# AJH_MM_v1_0.net
KiCad netlist of a schematic drawn in EAGLE
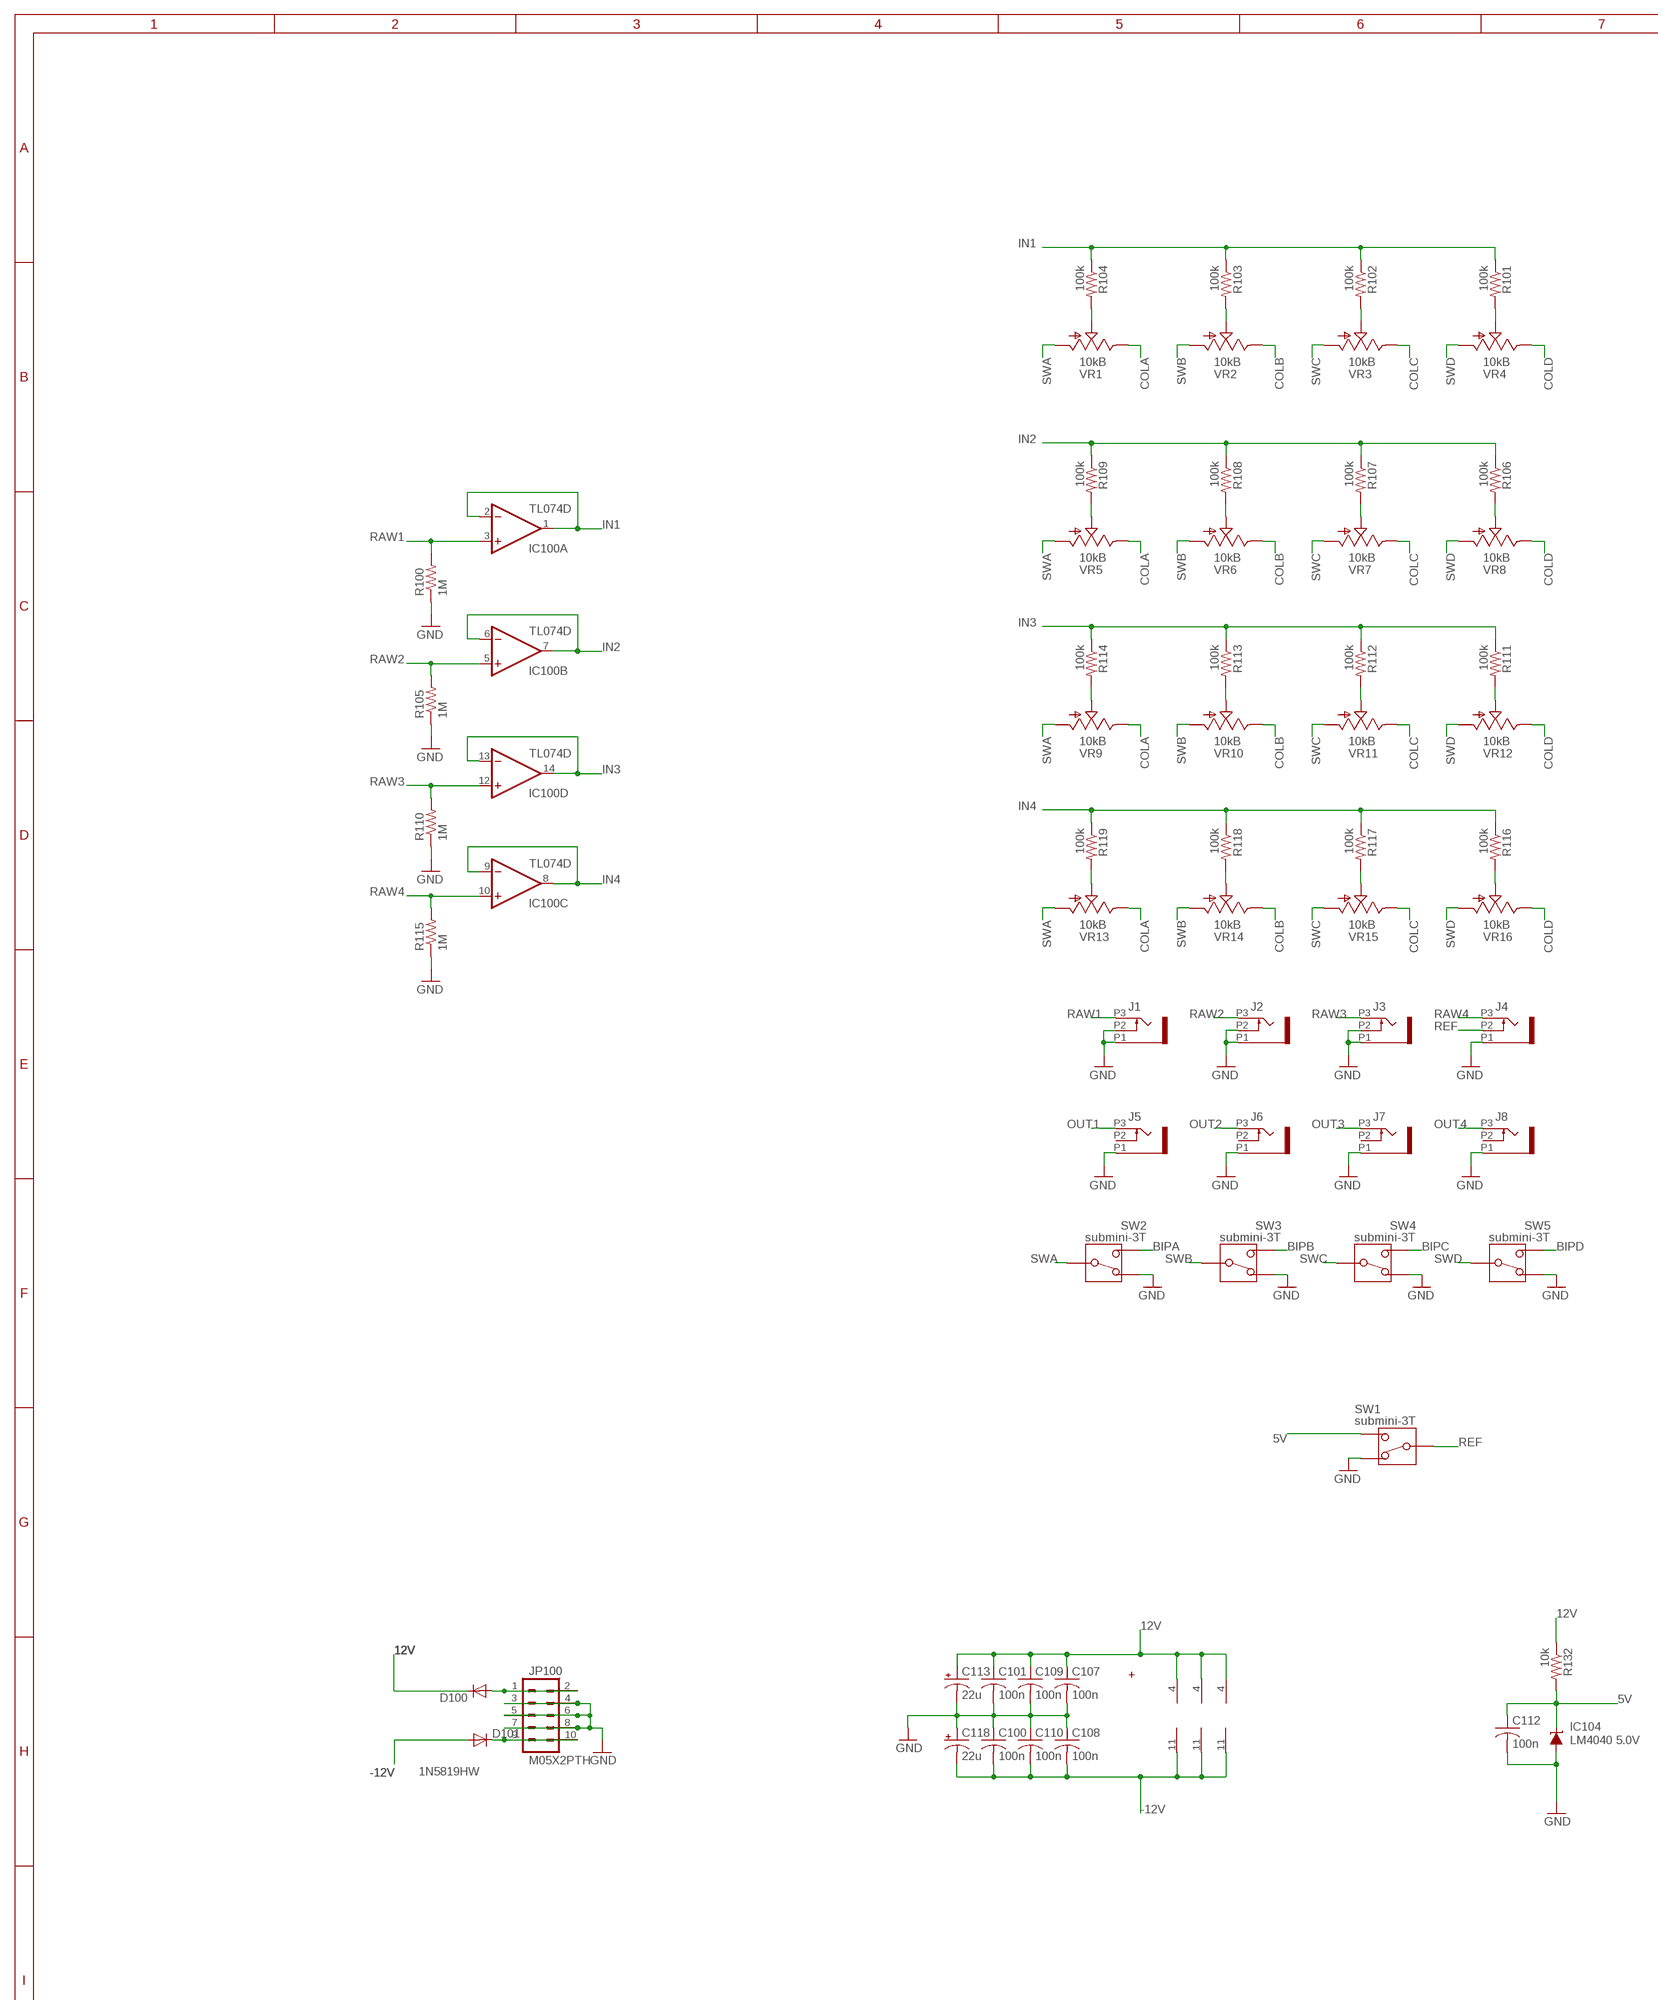
[diagram p0: schematic, sheet 1, part 1 of 2]
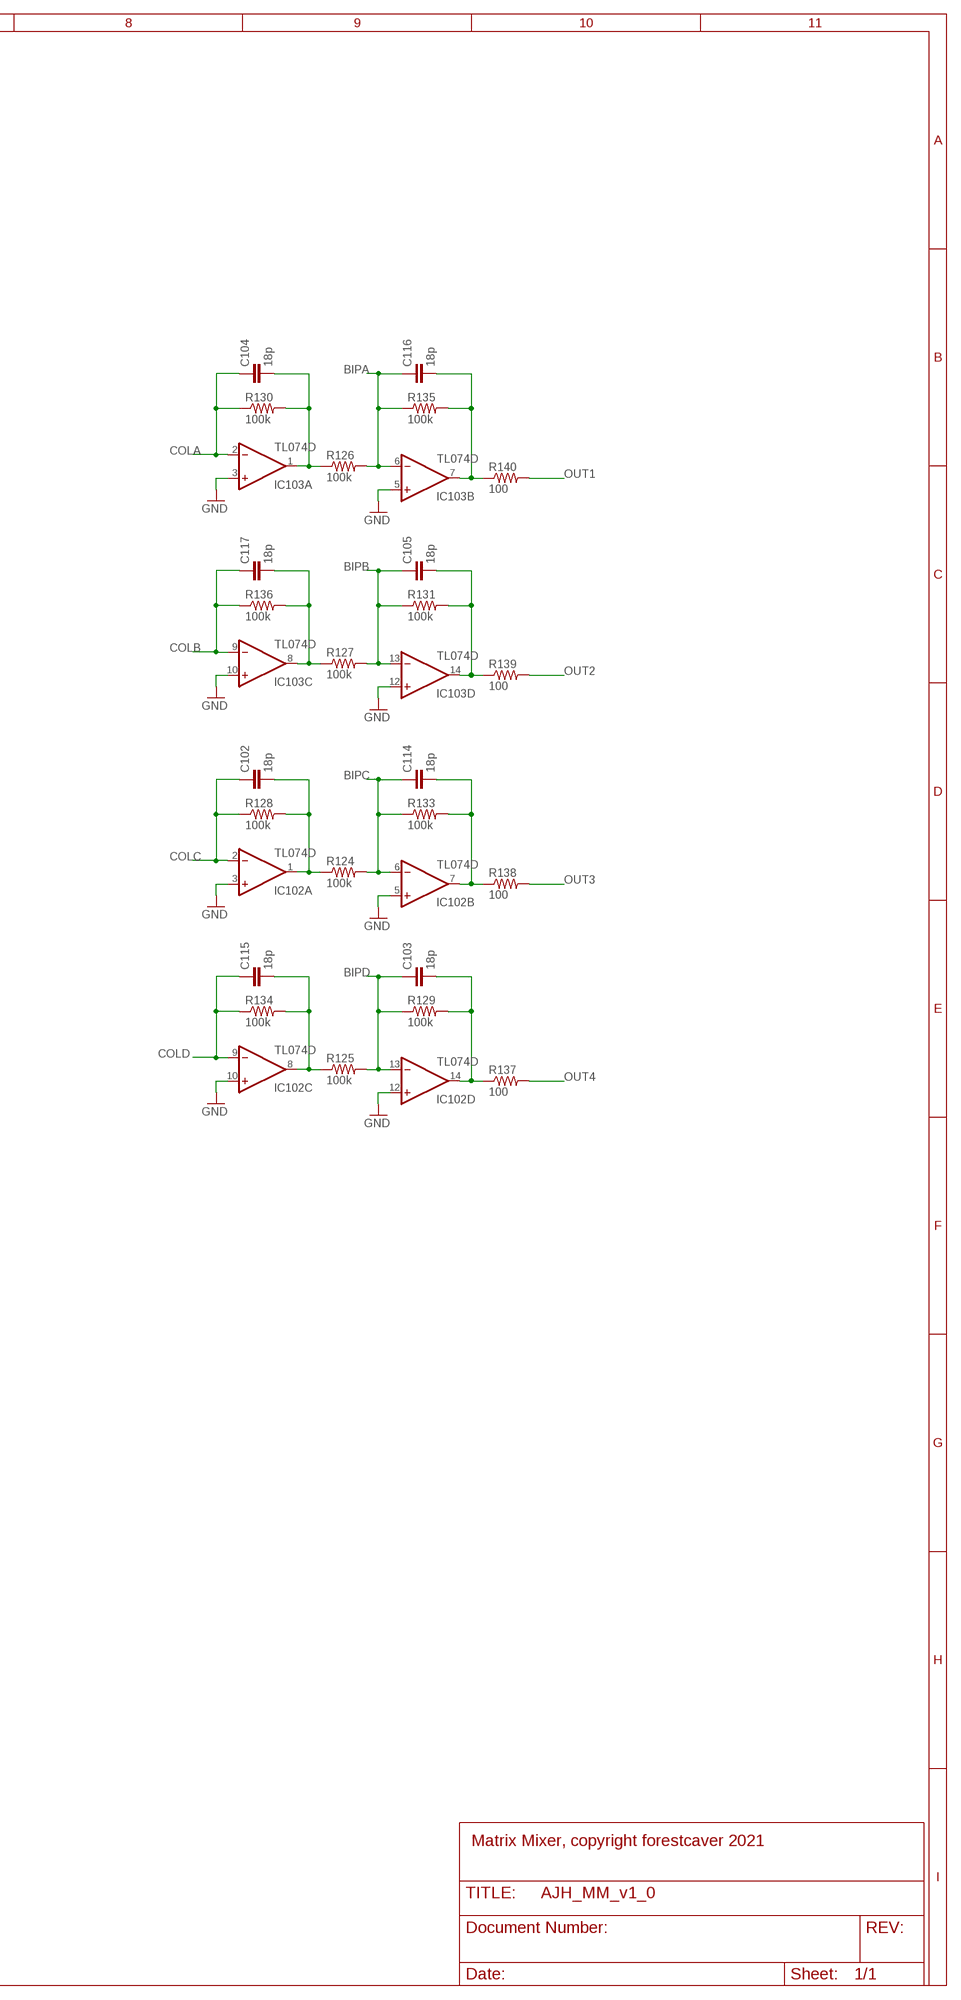
[diagram p1: schematic, sheet 1, part 2 of 2]

(export (version "E")
  (design (tool "Eeschema 10.0.6"))
  (components
    (comp (ref "C100")
      (value "100n")
      (footprint "eagle-import:C0603")
      (libsource (lib "eagle-import") (part "C-USC0603"))
    )
    (comp (ref "C101")
      (value "100n")
      (footprint "eagle-import:C0603")
      (libsource (lib "eagle-import") (part "C-USC0603"))
    )
    (comp (ref "C102")
      (value "18p")
      (footprint "eagle-import:C0603")
      (libsource (lib "eagle-import") (part "C-EUC0603"))
    )
    (comp (ref "C103")
      (value "18p")
      (footprint "eagle-import:C0603")
      (libsource (lib "eagle-import") (part "C-EUC0603"))
    )
    (comp (ref "C104")
      (value "18p")
      (footprint "eagle-import:C0603")
      (libsource (lib "eagle-import") (part "C-EUC0603"))
    )
    (comp (ref "C105")
      (value "18p")
      (footprint "eagle-import:C0603")
      (libsource (lib "eagle-import") (part "C-EUC0603"))
    )
    (comp (ref "C107")
      (value "100n")
      (footprint "eagle-import:C0603")
      (libsource (lib "eagle-import") (part "C-USC0603"))
    )
    (comp (ref "C108")
      (value "100n")
      (footprint "eagle-import:C0603")
      (libsource (lib "eagle-import") (part "C-USC0603"))
    )
    (comp (ref "C109")
      (value "100n")
      (footprint "eagle-import:C0603")
      (libsource (lib "eagle-import") (part "C-USC0603"))
    )
    (comp (ref "C110")
      (value "100n")
      (footprint "eagle-import:C0603")
      (libsource (lib "eagle-import") (part "C-USC0603"))
    )
    (comp (ref "C112")
      (value "100n")
      (footprint "eagle-import:C0603")
      (libsource (lib "eagle-import") (part "C-USC0603"))
    )
    (comp (ref "C113")
      (value "22u")
      (footprint "eagle-import:PANASONIC_B")
      (libsource (lib "eagle-import") (part "CPOL-USB"))
    )
    (comp (ref "C114")
      (value "18p")
      (footprint "eagle-import:C0603")
      (libsource (lib "eagle-import") (part "C-EUC0603"))
    )
    (comp (ref "C115")
      (value "18p")
      (footprint "eagle-import:C0603")
      (libsource (lib "eagle-import") (part "C-EUC0603"))
    )
    (comp (ref "C116")
      (value "18p")
      (footprint "eagle-import:C0603")
      (libsource (lib "eagle-import") (part "C-EUC0603"))
    )
    (comp (ref "C117")
      (value "18p")
      (footprint "eagle-import:C0603")
      (libsource (lib "eagle-import") (part "C-EUC0603"))
    )
    (comp (ref "C118")
      (value "22u")
      (footprint "eagle-import:PANASONIC_B")
      (libsource (lib "eagle-import") (part "CPOL-USB"))
    )
    (comp (ref "D100")
      (value "1N5819HW")
      (footprint "eagle-import:SOD123")
      (libsource (lib "eagle-import") (part "DIODE-SOD123"))
    )
    (comp (ref "D101")
      (value "1N5819HW")
      (footprint "eagle-import:SOD123")
      (libsource (lib "eagle-import") (part "DIODE-SOD123"))
    )
    (comp (ref "IC100")
      (value "TL074D")
      (footprint "eagle-import:SO14")
      (libsource (lib "eagle-import") (part "TL074D"))
    )
    (comp (ref "IC102")
      (value "TL074D")
      (footprint "eagle-import:SO14")
      (libsource (lib "eagle-import") (part "TL074D"))
    )
    (comp (ref "IC103")
      (value "TL074D")
      (footprint "eagle-import:SO14")
      (libsource (lib "eagle-import") (part "TL074D"))
    )
    (comp (ref "IC104")
      (value "LM4040 5.0V")
      (footprint "eagle-import:DBZ_R-PDSO-G3")
      (libsource (lib "eagle-import") (part "LM4041DBZC12"))
    )
    (comp (ref "J1")
      (value "PJ301_THONKICONN6")
      (footprint "eagle-import:WQP_PJ_301M6")
      (libsource (lib "eagle-import") (part "PJ301_THONKICONN6"))
    )
    (comp (ref "J2")
      (value "PJ301_THONKICONN6")
      (footprint "eagle-import:WQP_PJ_301M6")
      (libsource (lib "eagle-import") (part "PJ301_THONKICONN6"))
    )
    (comp (ref "J3")
      (value "PJ301_THONKICONN6")
      (footprint "eagle-import:WQP_PJ_301M6")
      (libsource (lib "eagle-import") (part "PJ301_THONKICONN6"))
    )
    (comp (ref "J4")
      (value "PJ301_THONKICONN6")
      (footprint "eagle-import:WQP_PJ_301M6")
      (libsource (lib "eagle-import") (part "PJ301_THONKICONN6"))
    )
    (comp (ref "J5")
      (value "PJ301_THONKICONN6")
      (footprint "eagle-import:WQP_PJ_301M6")
      (libsource (lib "eagle-import") (part "PJ301_THONKICONN6"))
    )
    (comp (ref "J6")
      (value "PJ301_THONKICONN6")
      (footprint "eagle-import:WQP_PJ_301M6")
      (libsource (lib "eagle-import") (part "PJ301_THONKICONN6"))
    )
    (comp (ref "J7")
      (value "PJ301_THONKICONN6")
      (footprint "eagle-import:WQP_PJ_301M6")
      (libsource (lib "eagle-import") (part "PJ301_THONKICONN6"))
    )
    (comp (ref "J8")
      (value "PJ301_THONKICONN6")
      (footprint "eagle-import:WQP_PJ_301M6")
      (libsource (lib "eagle-import") (part "PJ301_THONKICONN6"))
    )
    (comp (ref "JP100")
      (value "M05X2PTH")
      (footprint "eagle-import:AVR_ICSP")
      (libsource (lib "eagle-import") (part "M05X2PTH"))
    )
    (comp (ref "R100")
      (value "1M")
      (footprint "eagle-import:R0603")
      (libsource (lib "eagle-import") (part "R-US_R0603"))
    )
    (comp (ref "R101")
      (value "100k")
      (footprint "eagle-import:R0603")
      (libsource (lib "eagle-import") (part "R-US_R0603"))
    )
    (comp (ref "R102")
      (value "100k")
      (footprint "eagle-import:R0603")
      (libsource (lib "eagle-import") (part "R-US_R0603"))
    )
    (comp (ref "R103")
      (value "100k")
      (footprint "eagle-import:R0603")
      (libsource (lib "eagle-import") (part "R-US_R0603"))
    )
    (comp (ref "R104")
      (value "100k")
      (footprint "eagle-import:R0603")
      (libsource (lib "eagle-import") (part "R-US_R0603"))
    )
    (comp (ref "R105")
      (value "1M")
      (footprint "eagle-import:R0603")
      (libsource (lib "eagle-import") (part "R-US_R0603"))
    )
    (comp (ref "R106")
      (value "100k")
      (footprint "eagle-import:R0603")
      (libsource (lib "eagle-import") (part "R-US_R0603"))
    )
    (comp (ref "R107")
      (value "100k")
      (footprint "eagle-import:R0603")
      (libsource (lib "eagle-import") (part "R-US_R0603"))
    )
    (comp (ref "R108")
      (value "100k")
      (footprint "eagle-import:R0603")
      (libsource (lib "eagle-import") (part "R-US_R0603"))
    )
    (comp (ref "R109")
      (value "100k")
      (footprint "eagle-import:R0603")
      (libsource (lib "eagle-import") (part "R-US_R0603"))
    )
    (comp (ref "R110")
      (value "1M")
      (footprint "eagle-import:R0603")
      (libsource (lib "eagle-import") (part "R-US_R0603"))
    )
    (comp (ref "R111")
      (value "100k")
      (footprint "eagle-import:R0603")
      (libsource (lib "eagle-import") (part "R-US_R0603"))
    )
    (comp (ref "R112")
      (value "100k")
      (footprint "eagle-import:R0603")
      (libsource (lib "eagle-import") (part "R-US_R0603"))
    )
    (comp (ref "R113")
      (value "100k")
      (footprint "eagle-import:R0603")
      (libsource (lib "eagle-import") (part "R-US_R0603"))
    )
    (comp (ref "R114")
      (value "100k")
      (footprint "eagle-import:R0603")
      (libsource (lib "eagle-import") (part "R-US_R0603"))
    )
    (comp (ref "R115")
      (value "1M")
      (footprint "eagle-import:R0603")
      (libsource (lib "eagle-import") (part "R-US_R0603"))
    )
    (comp (ref "R116")
      (value "100k")
      (footprint "eagle-import:R0603")
      (libsource (lib "eagle-import") (part "R-US_R0603"))
    )
    (comp (ref "R117")
      (value "100k")
      (footprint "eagle-import:R0603")
      (libsource (lib "eagle-import") (part "R-US_R0603"))
    )
    (comp (ref "R118")
      (value "100k")
      (footprint "eagle-import:R0603")
      (libsource (lib "eagle-import") (part "R-US_R0603"))
    )
    (comp (ref "R119")
      (value "100k")
      (footprint "eagle-import:R0603")
      (libsource (lib "eagle-import") (part "R-US_R0603"))
    )
    (comp (ref "R124")
      (value "100k")
      (footprint "eagle-import:R0603")
      (libsource (lib "eagle-import") (part "R-US_R0603"))
    )
    (comp (ref "R125")
      (value "100k")
      (footprint "eagle-import:R0603")
      (libsource (lib "eagle-import") (part "R-US_R0603"))
    )
    (comp (ref "R126")
      (value "100k")
      (footprint "eagle-import:R0603")
      (libsource (lib "eagle-import") (part "R-US_R0603"))
    )
    (comp (ref "R127")
      (value "100k")
      (footprint "eagle-import:R0603")
      (libsource (lib "eagle-import") (part "R-US_R0603"))
    )
    (comp (ref "R128")
      (value "100k")
      (footprint "eagle-import:R0603")
      (libsource (lib "eagle-import") (part "R-US_R0603"))
    )
    (comp (ref "R129")
      (value "100k")
      (footprint "eagle-import:R0603")
      (libsource (lib "eagle-import") (part "R-US_R0603"))
    )
    (comp (ref "R130")
      (value "100k")
      (footprint "eagle-import:R0603")
      (libsource (lib "eagle-import") (part "R-US_R0603"))
    )
    (comp (ref "R131")
      (value "100k")
      (footprint "eagle-import:R0603")
      (libsource (lib "eagle-import") (part "R-US_R0603"))
    )
    (comp (ref "R132")
      (value "10k")
      (footprint "eagle-import:R0603")
      (libsource (lib "eagle-import") (part "R-US_R0603"))
    )
    (comp (ref "R133")
      (value "100k")
      (footprint "eagle-import:R0603")
      (libsource (lib "eagle-import") (part "R-US_R0603"))
    )
    (comp (ref "R134")
      (value "100k")
      (footprint "eagle-import:R0603")
      (libsource (lib "eagle-import") (part "R-US_R0603"))
    )
    (comp (ref "R135")
      (value "100k")
      (footprint "eagle-import:R0603")
      (libsource (lib "eagle-import") (part "R-US_R0603"))
    )
    (comp (ref "R136")
      (value "100k")
      (footprint "eagle-import:R0603")
      (libsource (lib "eagle-import") (part "R-US_R0603"))
    )
    (comp (ref "R137")
      (value "100")
      (footprint "eagle-import:R0603")
      (libsource (lib "eagle-import") (part "R-US_R0603"))
    )
    (comp (ref "R138")
      (value "100")
      (footprint "eagle-import:R0603")
      (libsource (lib "eagle-import") (part "R-US_R0603"))
    )
    (comp (ref "R139")
      (value "100")
      (footprint "eagle-import:R0603")
      (libsource (lib "eagle-import") (part "R-US_R0603"))
    )
    (comp (ref "R140")
      (value "100")
      (footprint "eagle-import:R0603")
      (libsource (lib "eagle-import") (part "R-US_R0603"))
    )
    (comp (ref "SW1")
      (value "submini-3T")
      (footprint "eagle-import:SPDT-SUB")
      (libsource (lib "eagle-import") (part "SPDTT"))
    )
    (comp (ref "SW2")
      (value "submini-3T")
      (footprint "eagle-import:SPDT-SUB")
      (libsource (lib "eagle-import") (part "SPDTT"))
    )
    (comp (ref "SW3")
      (value "submini-3T")
      (footprint "eagle-import:SPDT-SUB")
      (libsource (lib "eagle-import") (part "SPDTT"))
    )
    (comp (ref "SW4")
      (value "submini-3T")
      (footprint "eagle-import:SPDT-SUB")
      (libsource (lib "eagle-import") (part "SPDTT"))
    )
    (comp (ref "SW5")
      (value "submini-3T")
      (footprint "eagle-import:SPDT-SUB")
      (libsource (lib "eagle-import") (part "SPDTT"))
    )
    (comp (ref "VR1")
      (value "10kB")
      (footprint "eagle-import:ALPS_POT_VERTICAL")
      (libsource (lib "eagle-import") (part "POT_USVERTICAL"))
    )
    (comp (ref "VR2")
      (value "10kB")
      (footprint "eagle-import:ALPS_POT_VERTICAL")
      (libsource (lib "eagle-import") (part "POT_USVERTICAL"))
    )
    (comp (ref "VR3")
      (value "10kB")
      (footprint "eagle-import:ALPS_POT_VERTICAL")
      (libsource (lib "eagle-import") (part "POT_USVERTICAL"))
    )
    (comp (ref "VR4")
      (value "10kB")
      (footprint "eagle-import:ALPS_POT_VERTICAL")
      (libsource (lib "eagle-import") (part "POT_USVERTICAL"))
    )
    (comp (ref "VR5")
      (value "10kB")
      (footprint "eagle-import:ALPS_POT_VERTICAL")
      (libsource (lib "eagle-import") (part "POT_USVERTICAL"))
    )
    (comp (ref "VR6")
      (value "10kB")
      (footprint "eagle-import:ALPS_POT_VERTICAL")
      (libsource (lib "eagle-import") (part "POT_USVERTICAL"))
    )
    (comp (ref "VR7")
      (value "10kB")
      (footprint "eagle-import:ALPS_POT_VERTICAL")
      (libsource (lib "eagle-import") (part "POT_USVERTICAL"))
    )
    (comp (ref "VR8")
      (value "10kB")
      (footprint "eagle-import:ALPS_POT_VERTICAL")
      (libsource (lib "eagle-import") (part "POT_USVERTICAL"))
    )
    (comp (ref "VR9")
      (value "10kB")
      (footprint "eagle-import:ALPS_POT_VERTICAL")
      (libsource (lib "eagle-import") (part "POT_USVERTICAL"))
    )
    (comp (ref "VR10")
      (value "10kB")
      (footprint "eagle-import:ALPS_POT_VERTICAL")
      (libsource (lib "eagle-import") (part "POT_USVERTICAL"))
    )
    (comp (ref "VR11")
      (value "10kB")
      (footprint "eagle-import:ALPS_POT_VERTICAL")
      (libsource (lib "eagle-import") (part "POT_USVERTICAL"))
    )
    (comp (ref "VR12")
      (value "10kB")
      (footprint "eagle-import:ALPS_POT_VERTICAL")
      (libsource (lib "eagle-import") (part "POT_USVERTICAL"))
    )
    (comp (ref "VR13")
      (value "10kB")
      (footprint "eagle-import:ALPS_POT_VERTICAL")
      (libsource (lib "eagle-import") (part "POT_USVERTICAL"))
    )
    (comp (ref "VR14")
      (value "10kB")
      (footprint "eagle-import:ALPS_POT_VERTICAL")
      (libsource (lib "eagle-import") (part "POT_USVERTICAL"))
    )
    (comp (ref "VR15")
      (value "10kB")
      (footprint "eagle-import:ALPS_POT_VERTICAL")
      (libsource (lib "eagle-import") (part "POT_USVERTICAL"))
    )
    (comp (ref "VR16")
      (value "10kB")
      (footprint "eagle-import:ALPS_POT_VERTICAL")
      (libsource (lib "eagle-import") (part "POT_USVERTICAL"))
    )
  )
  (nets
    (net (code "1") (name "/-12V") (class "Default")
      (node (ref "C100") (pin "2") (pinfunction "2_2") (pintype "passive"))
      (node (ref "C108") (pin "2") (pinfunction "2_2") (pintype "passive"))
      (node (ref "C110") (pin "2") (pinfunction "2_2") (pintype "passive"))
      (node (ref "C118") (pin "-") (pinfunction "-_-") (pintype "passive"))
      (node (ref "D101") (pin "A") (pinfunction "A_A") (pintype "passive"))
      (node (ref "IC100") (pin "11") (pinfunction "V-_11") (pintype "power_in"))
      (node (ref "IC102") (pin "11") (pinfunction "V-_11") (pintype "power_in"))
      (node (ref "IC103") (pin "11") (pinfunction "V-_11") (pintype "power_in"))
    )
    (net (code "2") (name "/5V") (class "Default")
      (node (ref "C112") (pin "1") (pinfunction "1_1") (pintype "passive"))
      (node (ref "IC104") (pin "1") (pinfunction "C_1") (pintype "passive"))
      (node (ref "R132") (pin "2") (pinfunction "2_2") (pintype "passive"))
      (node (ref "SW1") (pin "P$1") (pinfunction "P$1_P$1") (pintype "passive"))
    )
    (net (code "3") (name "/12V") (class "Default")
      (node (ref "C101") (pin "1") (pinfunction "1_1") (pintype "passive"))
      (node (ref "C107") (pin "1") (pinfunction "1_1") (pintype "passive"))
      (node (ref "C109") (pin "1") (pinfunction "1_1") (pintype "passive"))
      (node (ref "C113") (pin "+") (pinfunction "+_+") (pintype "passive"))
      (node (ref "D100") (pin "C") (pinfunction "C_C") (pintype "passive"))
      (node (ref "IC100") (pin "4") (pinfunction "V+_4") (pintype "power_in"))
      (node (ref "IC102") (pin "4") (pinfunction "V+_4") (pintype "power_in"))
      (node (ref "IC103") (pin "4") (pinfunction "V+_4") (pintype "power_in"))
      (node (ref "R132") (pin "1") (pinfunction "1_1") (pintype "passive"))
    )
    (net (code "4") (name "/BIPA") (class "Default")
      (node (ref "C116") (pin "1") (pinfunction "1_1") (pintype "passive"))
      (node (ref "IC103") (pin "6") (pinfunction "-IN_6") (pintype "input"))
      (node (ref "R126") (pin "2") (pinfunction "2_2") (pintype "passive"))
      (node (ref "R135") (pin "1") (pinfunction "1_1") (pintype "passive"))
      (node (ref "SW2") (pin "P$1") (pinfunction "P$1_P$1") (pintype "passive"))
    )
    (net (code "5") (name "/BIPB") (class "Default")
      (node (ref "C105") (pin "1") (pinfunction "1_1") (pintype "passive"))
      (node (ref "IC103") (pin "13") (pinfunction "-IN_13") (pintype "input"))
      (node (ref "R127") (pin "2") (pinfunction "2_2") (pintype "passive"))
      (node (ref "R131") (pin "1") (pinfunction "1_1") (pintype "passive"))
      (node (ref "SW3") (pin "P$1") (pinfunction "P$1_P$1") (pintype "passive"))
    )
    (net (code "6") (name "/BIPC") (class "Default")
      (node (ref "C114") (pin "1") (pinfunction "1_1") (pintype "passive"))
      (node (ref "IC102") (pin "6") (pinfunction "-IN_6") (pintype "input"))
      (node (ref "R124") (pin "2") (pinfunction "2_2") (pintype "passive"))
      (node (ref "R133") (pin "1") (pinfunction "1_1") (pintype "passive"))
      (node (ref "SW4") (pin "P$1") (pinfunction "P$1_P$1") (pintype "passive"))
    )
    (net (code "7") (name "/BIPD") (class "Default")
      (node (ref "C103") (pin "1") (pinfunction "1_1") (pintype "passive"))
      (node (ref "IC102") (pin "13") (pinfunction "-IN_13") (pintype "input"))
      (node (ref "R125") (pin "2") (pinfunction "2_2") (pintype "passive"))
      (node (ref "R129") (pin "1") (pinfunction "1_1") (pintype "passive"))
      (node (ref "SW5") (pin "P$1") (pinfunction "P$1_P$1") (pintype "passive"))
    )
    (net (code "8") (name "/COLA") (class "Default")
      (node (ref "C104") (pin "1") (pinfunction "1_1") (pintype "passive"))
      (node (ref "IC103") (pin "2") (pinfunction "-IN_2") (pintype "input"))
      (node (ref "R130") (pin "1") (pinfunction "1_1") (pintype "passive"))
      (node (ref "VR1") (pin "P$1") (pinfunction "E_P$1") (pintype "passive"))
      (node (ref "VR13") (pin "P$1") (pinfunction "E_P$1") (pintype "passive"))
      (node (ref "VR5") (pin "P$1") (pinfunction "E_P$1") (pintype "passive"))
      (node (ref "VR9") (pin "P$1") (pinfunction "E_P$1") (pintype "passive"))
    )
    (net (code "9") (name "/COLB") (class "Default")
      (node (ref "C117") (pin "1") (pinfunction "1_1") (pintype "passive"))
      (node (ref "IC103") (pin "9") (pinfunction "-IN_9") (pintype "input"))
      (node (ref "R136") (pin "1") (pinfunction "1_1") (pintype "passive"))
      (node (ref "VR10") (pin "P$1") (pinfunction "E_P$1") (pintype "passive"))
      (node (ref "VR14") (pin "P$1") (pinfunction "E_P$1") (pintype "passive"))
      (node (ref "VR2") (pin "P$1") (pinfunction "E_P$1") (pintype "passive"))
      (node (ref "VR6") (pin "P$1") (pinfunction "E_P$1") (pintype "passive"))
    )
    (net (code "10") (name "/COLC") (class "Default")
      (node (ref "C102") (pin "1") (pinfunction "1_1") (pintype "passive"))
      (node (ref "IC102") (pin "2") (pinfunction "-IN_2") (pintype "input"))
      (node (ref "R128") (pin "1") (pinfunction "1_1") (pintype "passive"))
      (node (ref "VR11") (pin "P$1") (pinfunction "E_P$1") (pintype "passive"))
      (node (ref "VR15") (pin "P$1") (pinfunction "E_P$1") (pintype "passive"))
      (node (ref "VR3") (pin "P$1") (pinfunction "E_P$1") (pintype "passive"))
      (node (ref "VR7") (pin "P$1") (pinfunction "E_P$1") (pintype "passive"))
    )
    (net (code "11") (name "/COLD") (class "Default")
      (node (ref "C115") (pin "1") (pinfunction "1_1") (pintype "passive"))
      (node (ref "IC102") (pin "9") (pinfunction "-IN_9") (pintype "input"))
      (node (ref "R134") (pin "1") (pinfunction "1_1") (pintype "passive"))
      (node (ref "VR12") (pin "P$1") (pinfunction "E_P$1") (pintype "passive"))
      (node (ref "VR16") (pin "P$1") (pinfunction "E_P$1") (pintype "passive"))
      (node (ref "VR4") (pin "P$1") (pinfunction "E_P$1") (pintype "passive"))
      (node (ref "VR8") (pin "P$1") (pinfunction "E_P$1") (pintype "passive"))
    )
    (net (code "12") (name "/IN1") (class "Default")
      (node (ref "IC100") (pin "1") (pinfunction "OUT_1") (pintype "output"))
      (node (ref "IC100") (pin "2") (pinfunction "-IN_2") (pintype "input"))
      (node (ref "R101") (pin "1") (pinfunction "1_1") (pintype "passive"))
      (node (ref "R102") (pin "1") (pinfunction "1_1") (pintype "passive"))
      (node (ref "R103") (pin "1") (pinfunction "1_1") (pintype "passive"))
      (node (ref "R104") (pin "1") (pinfunction "1_1") (pintype "passive"))
    )
    (net (code "13") (name "/IN2") (class "Default")
      (node (ref "IC100") (pin "6") (pinfunction "-IN_6") (pintype "input"))
      (node (ref "IC100") (pin "7") (pinfunction "OUT_7") (pintype "output"))
      (node (ref "R106") (pin "1") (pinfunction "1_1") (pintype "passive"))
      (node (ref "R107") (pin "1") (pinfunction "1_1") (pintype "passive"))
      (node (ref "R108") (pin "1") (pinfunction "1_1") (pintype "passive"))
      (node (ref "R109") (pin "1") (pinfunction "1_1") (pintype "passive"))
    )
    (net (code "14") (name "/IN3") (class "Default")
      (node (ref "IC100") (pin "13") (pinfunction "-IN_13") (pintype "input"))
      (node (ref "IC100") (pin "14") (pinfunction "OUT_14") (pintype "output"))
      (node (ref "R111") (pin "1") (pinfunction "1_1") (pintype "passive"))
      (node (ref "R112") (pin "1") (pinfunction "1_1") (pintype "passive"))
      (node (ref "R113") (pin "1") (pinfunction "1_1") (pintype "passive"))
      (node (ref "R114") (pin "1") (pinfunction "1_1") (pintype "passive"))
    )
    (net (code "15") (name "/IN4") (class "Default")
      (node (ref "IC100") (pin "8") (pinfunction "OUT_8") (pintype "output"))
      (node (ref "IC100") (pin "9") (pinfunction "-IN_9") (pintype "input"))
      (node (ref "R116") (pin "1") (pinfunction "1_1") (pintype "passive"))
      (node (ref "R117") (pin "1") (pinfunction "1_1") (pintype "passive"))
      (node (ref "R118") (pin "1") (pinfunction "1_1") (pintype "passive"))
      (node (ref "R119") (pin "1") (pinfunction "1_1") (pintype "passive"))
    )
    (net (code "16") (name "/OUT1") (class "Default")
      (node (ref "J5") (pin "P3") (pinfunction "3_P3") (pintype "passive"))
      (node (ref "R140") (pin "2") (pinfunction "2_2") (pintype "passive"))
    )
    (net (code "17") (name "/OUT2") (class "Default")
      (node (ref "J6") (pin "P3") (pinfunction "3_P3") (pintype "passive"))
      (node (ref "R139") (pin "2") (pinfunction "2_2") (pintype "passive"))
    )
    (net (code "18") (name "/OUT3") (class "Default")
      (node (ref "J7") (pin "P3") (pinfunction "3_P3") (pintype "passive"))
      (node (ref "R138") (pin "2") (pinfunction "2_2") (pintype "passive"))
    )
    (net (code "19") (name "/OUT4") (class "Default")
      (node (ref "J8") (pin "P3") (pinfunction "3_P3") (pintype "passive"))
      (node (ref "R137") (pin "2") (pinfunction "2_2") (pintype "passive"))
    )
    (net (code "20") (name "/RAW1") (class "Default")
      (node (ref "IC100") (pin "3") (pinfunction "+IN_3") (pintype "input"))
      (node (ref "J1") (pin "P3") (pinfunction "3_P3") (pintype "passive"))
      (node (ref "R100") (pin "2") (pinfunction "2_2") (pintype "passive"))
    )
    (net (code "21") (name "/RAW2") (class "Default")
      (node (ref "IC100") (pin "5") (pinfunction "+IN_5") (pintype "input"))
      (node (ref "J2") (pin "P3") (pinfunction "3_P3") (pintype "passive"))
      (node (ref "R105") (pin "2") (pinfunction "2_2") (pintype "passive"))
    )
    (net (code "22") (name "/RAW3") (class "Default")
      (node (ref "IC100") (pin "12") (pinfunction "+IN_12") (pintype "input"))
      (node (ref "J3") (pin "P3") (pinfunction "3_P3") (pintype "passive"))
      (node (ref "R110") (pin "2") (pinfunction "2_2") (pintype "passive"))
    )
    (net (code "23") (name "/RAW4") (class "Default")
      (node (ref "IC100") (pin "10") (pinfunction "+IN_10") (pintype "input"))
      (node (ref "J4") (pin "P3") (pinfunction "3_P3") (pintype "passive"))
      (node (ref "R115") (pin "2") (pinfunction "2_2") (pintype "passive"))
    )
    (net (code "24") (name "/REF") (class "Default")
      (node (ref "J4") (pin "P2") (pinfunction "2_P2") (pintype "passive"))
      (node (ref "SW1") (pin "P$2") (pinfunction "P$2_P$2") (pintype "passive"))
    )
    (net (code "25") (name "/SWA") (class "Default")
      (node (ref "SW2") (pin "P$2") (pinfunction "P$2_P$2") (pintype "passive"))
      (node (ref "VR1") (pin "P$3") (pinfunction "A_P$3") (pintype "passive"))
      (node (ref "VR13") (pin "P$3") (pinfunction "A_P$3") (pintype "passive"))
      (node (ref "VR5") (pin "P$3") (pinfunction "A_P$3") (pintype "passive"))
      (node (ref "VR9") (pin "P$3") (pinfunction "A_P$3") (pintype "passive"))
    )
    (net (code "26") (name "/SWB") (class "Default")
      (node (ref "SW3") (pin "P$2") (pinfunction "P$2_P$2") (pintype "passive"))
      (node (ref "VR10") (pin "P$3") (pinfunction "A_P$3") (pintype "passive"))
      (node (ref "VR14") (pin "P$3") (pinfunction "A_P$3") (pintype "passive"))
      (node (ref "VR2") (pin "P$3") (pinfunction "A_P$3") (pintype "passive"))
      (node (ref "VR6") (pin "P$3") (pinfunction "A_P$3") (pintype "passive"))
    )
    (net (code "27") (name "/SWC") (class "Default")
      (node (ref "SW4") (pin "P$2") (pinfunction "P$2_P$2") (pintype "passive"))
      (node (ref "VR11") (pin "P$3") (pinfunction "A_P$3") (pintype "passive"))
      (node (ref "VR15") (pin "P$3") (pinfunction "A_P$3") (pintype "passive"))
      (node (ref "VR3") (pin "P$3") (pinfunction "A_P$3") (pintype "passive"))
      (node (ref "VR7") (pin "P$3") (pinfunction "A_P$3") (pintype "passive"))
    )
    (net (code "28") (name "/SWD") (class "Default")
      (node (ref "SW5") (pin "P$2") (pinfunction "P$2_P$2") (pintype "passive"))
      (node (ref "VR12") (pin "P$3") (pinfunction "A_P$3") (pintype "passive"))
      (node (ref "VR16") (pin "P$3") (pinfunction "A_P$3") (pintype "passive"))
      (node (ref "VR4") (pin "P$3") (pinfunction "A_P$3") (pintype "passive"))
      (node (ref "VR8") (pin "P$3") (pinfunction "A_P$3") (pintype "passive"))
    )
    (net (code "29") (name "GND") (class "Default")
      (node (ref "C100") (pin "1") (pinfunction "1_1") (pintype "passive"))
      (node (ref "C101") (pin "2") (pinfunction "2_2") (pintype "passive"))
      (node (ref "C107") (pin "2") (pinfunction "2_2") (pintype "passive"))
      (node (ref "C108") (pin "1") (pinfunction "1_1") (pintype "passive"))
      (node (ref "C109") (pin "2") (pinfunction "2_2") (pintype "passive"))
      (node (ref "C110") (pin "1") (pinfunction "1_1") (pintype "passive"))
      (node (ref "C112") (pin "2") (pinfunction "2_2") (pintype "passive"))
      (node (ref "C113") (pin "-") (pinfunction "-_-") (pintype "passive"))
      (node (ref "C118") (pin "+") (pinfunction "+_+") (pintype "passive"))
      (node (ref "IC102") (pin "10") (pinfunction "+IN_10") (pintype "input"))
      (node (ref "IC102") (pin "12") (pinfunction "+IN_12") (pintype "input"))
      (node (ref "IC102") (pin "3") (pinfunction "+IN_3") (pintype "input"))
      (node (ref "IC102") (pin "5") (pinfunction "+IN_5") (pintype "input"))
      (node (ref "IC103") (pin "10") (pinfunction "+IN_10") (pintype "input"))
      (node (ref "IC103") (pin "12") (pinfunction "+IN_12") (pintype "input"))
      (node (ref "IC103") (pin "3") (pinfunction "+IN_3") (pintype "input"))
      (node (ref "IC103") (pin "5") (pinfunction "+IN_5") (pintype "input"))
      (node (ref "IC104") (pin "2") (pinfunction "A_2") (pintype "passive"))
      (node (ref "J1") (pin "P1") (pinfunction "1_P1") (pintype "passive"))
      (node (ref "J1") (pin "P2") (pinfunction "2_P2") (pintype "passive"))
      (node (ref "J2") (pin "P1") (pinfunction "1_P1") (pintype "passive"))
      (node (ref "J2") (pin "P2") (pinfunction "2_P2") (pintype "passive"))
      (node (ref "J3") (pin "P1") (pinfunction "1_P1") (pintype "passive"))
      (node (ref "J3") (pin "P2") (pinfunction "2_P2") (pintype "passive"))
      (node (ref "J4") (pin "P1") (pinfunction "1_P1") (pintype "passive"))
      (node (ref "J5") (pin "P1") (pinfunction "1_P1") (pintype "passive"))
      (node (ref "J6") (pin "P1") (pinfunction "1_P1") (pintype "passive"))
      (node (ref "J7") (pin "P1") (pinfunction "1_P1") (pintype "passive"))
      (node (ref "J8") (pin "P1") (pinfunction "1_P1") (pintype "passive"))
      (node (ref "JP100") (pin "3") (pinfunction "3_3") (pintype "passive"))
      (node (ref "JP100") (pin "4") (pinfunction "4_4") (pintype "passive"))
      (node (ref "JP100") (pin "5") (pinfunction "5_5") (pintype "passive"))
      (node (ref "JP100") (pin "6") (pinfunction "6_6") (pintype "passive"))
      (node (ref "JP100") (pin "7") (pinfunction "7_7") (pintype "passive"))
      (node (ref "JP100") (pin "8") (pinfunction "8_8") (pintype "passive"))
      (node (ref "R100") (pin "1") (pinfunction "1_1") (pintype "passive"))
      (node (ref "R105") (pin "1") (pinfunction "1_1") (pintype "passive"))
      (node (ref "R110") (pin "1") (pinfunction "1_1") (pintype "passive"))
      (node (ref "R115") (pin "1") (pinfunction "1_1") (pintype "passive"))
      (node (ref "SW1") (pin "P$3") (pinfunction "P$3_P$3") (pintype "passive"))
      (node (ref "SW2") (pin "P$3") (pinfunction "P$3_P$3") (pintype "passive"))
      (node (ref "SW3") (pin "P$3") (pinfunction "P$3_P$3") (pintype "passive"))
      (node (ref "SW4") (pin "P$3") (pinfunction "P$3_P$3") (pintype "passive"))
      (node (ref "SW5") (pin "P$3") (pinfunction "P$3_P$3") (pintype "passive"))
    )
    (net (code "30") (name "Net-(D100-PadA)") (class "Default")
      (node (ref "D100") (pin "A") (pinfunction "A_A") (pintype "passive"))
      (node (ref "JP100") (pin "1") (pinfunction "1_1") (pintype "passive"))
      (node (ref "JP100") (pin "2") (pinfunction "2_2") (pintype "passive"))
    )
    (net (code "31") (name "Net-(D101-PadC)") (class "Default")
      (node (ref "D101") (pin "C") (pinfunction "C_C") (pintype "passive"))
      (node (ref "JP100") (pin "10") (pinfunction "10_10") (pintype "passive"))
      (node (ref "JP100") (pin "9") (pinfunction "9_9") (pintype "passive"))
    )
    (net (code "32") (name "Net-(IC102A-OUT)") (class "Default")
      (node (ref "C102") (pin "2") (pinfunction "2_2") (pintype "passive"))
      (node (ref "IC102") (pin "1") (pinfunction "OUT_1") (pintype "output"))
      (node (ref "R124") (pin "1") (pinfunction "1_1") (pintype "passive"))
      (node (ref "R128") (pin "2") (pinfunction "2_2") (pintype "passive"))
    )
    (net (code "33") (name "Net-(IC102B-OUT)") (class "Default")
      (node (ref "C114") (pin "2") (pinfunction "2_2") (pintype "passive"))
      (node (ref "IC102") (pin "7") (pinfunction "OUT_7") (pintype "output"))
      (node (ref "R133") (pin "2") (pinfunction "2_2") (pintype "passive"))
      (node (ref "R138") (pin "1") (pinfunction "1_1") (pintype "passive"))
    )
    (net (code "34") (name "Net-(IC102C-OUT)") (class "Default")
      (node (ref "C115") (pin "2") (pinfunction "2_2") (pintype "passive"))
      (node (ref "IC102") (pin "8") (pinfunction "OUT_8") (pintype "output"))
      (node (ref "R125") (pin "1") (pinfunction "1_1") (pintype "passive"))
      (node (ref "R134") (pin "2") (pinfunction "2_2") (pintype "passive"))
    )
    (net (code "35") (name "Net-(IC102D-OUT)") (class "Default")
      (node (ref "C103") (pin "2") (pinfunction "2_2") (pintype "passive"))
      (node (ref "IC102") (pin "14") (pinfunction "OUT_14") (pintype "output"))
      (node (ref "R129") (pin "2") (pinfunction "2_2") (pintype "passive"))
      (node (ref "R137") (pin "1") (pinfunction "1_1") (pintype "passive"))
    )
    (net (code "36") (name "Net-(IC103A-OUT)") (class "Default")
      (node (ref "C104") (pin "2") (pinfunction "2_2") (pintype "passive"))
      (node (ref "IC103") (pin "1") (pinfunction "OUT_1") (pintype "output"))
      (node (ref "R126") (pin "1") (pinfunction "1_1") (pintype "passive"))
      (node (ref "R130") (pin "2") (pinfunction "2_2") (pintype "passive"))
    )
    (net (code "37") (name "Net-(IC103B-OUT)") (class "Default")
      (node (ref "C116") (pin "2") (pinfunction "2_2") (pintype "passive"))
      (node (ref "IC103") (pin "7") (pinfunction "OUT_7") (pintype "output"))
      (node (ref "R135") (pin "2") (pinfunction "2_2") (pintype "passive"))
      (node (ref "R140") (pin "1") (pinfunction "1_1") (pintype "passive"))
    )
    (net (code "38") (name "Net-(IC103C-OUT)") (class "Default")
      (node (ref "C117") (pin "2") (pinfunction "2_2") (pintype "passive"))
      (node (ref "IC103") (pin "8") (pinfunction "OUT_8") (pintype "output"))
      (node (ref "R127") (pin "1") (pinfunction "1_1") (pintype "passive"))
      (node (ref "R136") (pin "2") (pinfunction "2_2") (pintype "passive"))
    )
    (net (code "39") (name "Net-(IC103D-OUT)") (class "Default")
      (node (ref "C105") (pin "2") (pinfunction "2_2") (pintype "passive"))
      (node (ref "IC103") (pin "14") (pinfunction "OUT_14") (pintype "output"))
      (node (ref "R131") (pin "2") (pinfunction "2_2") (pintype "passive"))
      (node (ref "R139") (pin "1") (pinfunction "1_1") (pintype "passive"))
    )
    (net (code "40") (name "Net-(VR1-S)") (class "Default")
      (node (ref "R104") (pin "2") (pinfunction "2_2") (pintype "passive"))
      (node (ref "VR1") (pin "P$2") (pinfunction "S_P$2") (pintype "passive"))
    )
    (net (code "41") (name "Net-(VR2-S)") (class "Default")
      (node (ref "R103") (pin "2") (pinfunction "2_2") (pintype "passive"))
      (node (ref "VR2") (pin "P$2") (pinfunction "S_P$2") (pintype "passive"))
    )
    (net (code "42") (name "Net-(VR3-S)") (class "Default")
      (node (ref "R102") (pin "2") (pinfunction "2_2") (pintype "passive"))
      (node (ref "VR3") (pin "P$2") (pinfunction "S_P$2") (pintype "passive"))
    )
    (net (code "43") (name "Net-(VR4-S)") (class "Default")
      (node (ref "R101") (pin "2") (pinfunction "2_2") (pintype "passive"))
      (node (ref "VR4") (pin "P$2") (pinfunction "S_P$2") (pintype "passive"))
    )
    (net (code "44") (name "Net-(VR5-S)") (class "Default")
      (node (ref "R109") (pin "2") (pinfunction "2_2") (pintype "passive"))
      (node (ref "VR5") (pin "P$2") (pinfunction "S_P$2") (pintype "passive"))
    )
    (net (code "45") (name "Net-(VR6-S)") (class "Default")
      (node (ref "R108") (pin "2") (pinfunction "2_2") (pintype "passive"))
      (node (ref "VR6") (pin "P$2") (pinfunction "S_P$2") (pintype "passive"))
    )
    (net (code "46") (name "Net-(VR7-S)") (class "Default")
      (node (ref "R107") (pin "2") (pinfunction "2_2") (pintype "passive"))
      (node (ref "VR7") (pin "P$2") (pinfunction "S_P$2") (pintype "passive"))
    )
    (net (code "47") (name "Net-(VR8-S)") (class "Default")
      (node (ref "R106") (pin "2") (pinfunction "2_2") (pintype "passive"))
      (node (ref "VR8") (pin "P$2") (pinfunction "S_P$2") (pintype "passive"))
    )
    (net (code "48") (name "Net-(VR9-S)") (class "Default")
      (node (ref "R114") (pin "2") (pinfunction "2_2") (pintype "passive"))
      (node (ref "VR9") (pin "P$2") (pinfunction "S_P$2") (pintype "passive"))
    )
    (net (code "49") (name "Net-(VR10-S)") (class "Default")
      (node (ref "R113") (pin "2") (pinfunction "2_2") (pintype "passive"))
      (node (ref "VR10") (pin "P$2") (pinfunction "S_P$2") (pintype "passive"))
    )
    (net (code "50") (name "Net-(VR11-S)") (class "Default")
      (node (ref "R112") (pin "2") (pinfunction "2_2") (pintype "passive"))
      (node (ref "VR11") (pin "P$2") (pinfunction "S_P$2") (pintype "passive"))
    )
    (net (code "51") (name "Net-(VR12-S)") (class "Default")
      (node (ref "R111") (pin "2") (pinfunction "2_2") (pintype "passive"))
      (node (ref "VR12") (pin "P$2") (pinfunction "S_P$2") (pintype "passive"))
    )
    (net (code "52") (name "Net-(VR13-S)") (class "Default")
      (node (ref "R119") (pin "2") (pinfunction "2_2") (pintype "passive"))
      (node (ref "VR13") (pin "P$2") (pinfunction "S_P$2") (pintype "passive"))
    )
    (net (code "53") (name "Net-(VR14-S)") (class "Default")
      (node (ref "R118") (pin "2") (pinfunction "2_2") (pintype "passive"))
      (node (ref "VR14") (pin "P$2") (pinfunction "S_P$2") (pintype "passive"))
    )
    (net (code "54") (name "Net-(VR15-S)") (class "Default")
      (node (ref "R117") (pin "2") (pinfunction "2_2") (pintype "passive"))
      (node (ref "VR15") (pin "P$2") (pinfunction "S_P$2") (pintype "passive"))
    )
    (net (code "55") (name "Net-(VR16-S)") (class "Default")
      (node (ref "R116") (pin "2") (pinfunction "2_2") (pintype "passive"))
      (node (ref "VR16") (pin "P$2") (pinfunction "S_P$2") (pintype "passive"))
    )
    (net (code "56") (name "unconnected-(J5-2-PadP2)") (class "Default")
      (node (ref "J5") (pin "P2") (pinfunction "2_P2") (pintype "passive"))
    )
    (net (code "57") (name "unconnected-(J6-2-PadP2)") (class "Default")
      (node (ref "J6") (pin "P2") (pinfunction "2_P2") (pintype "passive"))
    )
    (net (code "58") (name "unconnected-(J7-2-PadP2)") (class "Default")
      (node (ref "J7") (pin "P2") (pinfunction "2_P2") (pintype "passive"))
    )
    (net (code "59") (name "unconnected-(J8-2-PadP2)") (class "Default")
      (node (ref "J8") (pin "P2") (pinfunction "2_P2") (pintype "passive"))
    )
  )
)
